# Bravo-Flash_Programmer.net
KiCad netlist of a schematic drawn in EasyEDA
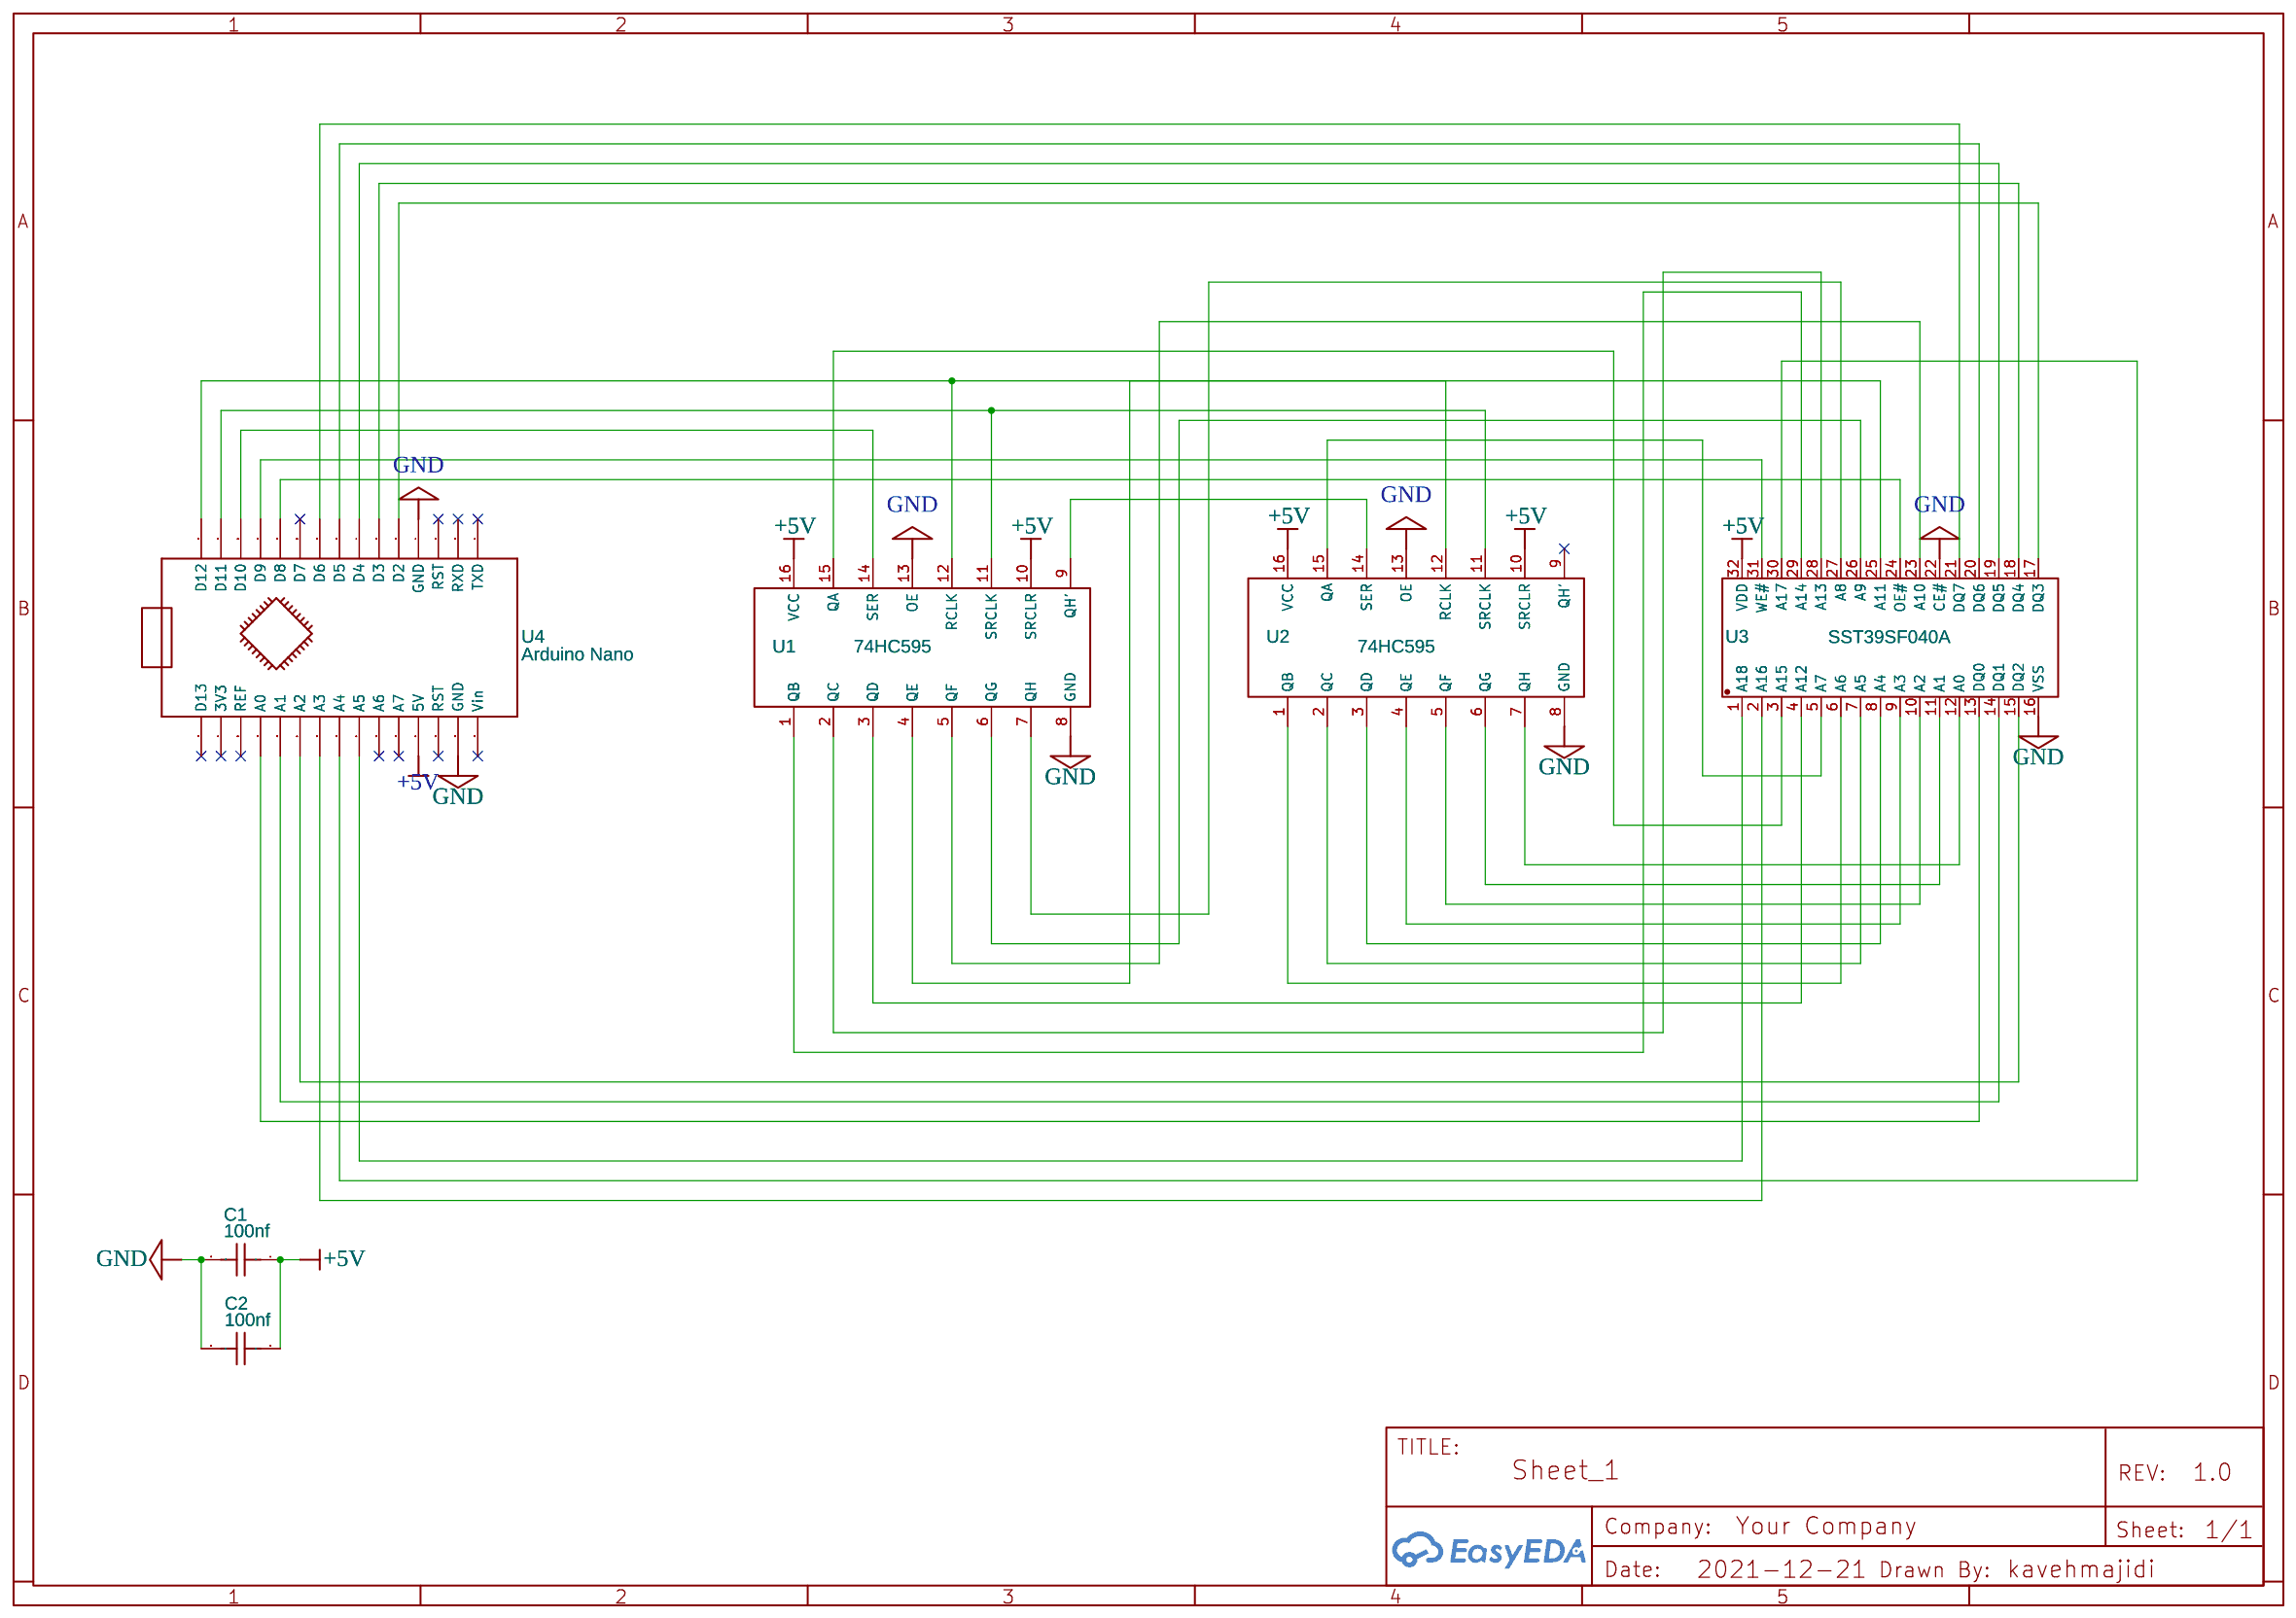
[diagram p0: schematic sheet]

(export (version "E")
  (design (tool "Eeschema 10.0.6"))
  (components
    (comp (ref "C1")
      (value "100nf")
      (fields
        (field (name "BOM_Manufacturer Part") "CC45SL3AD220JYVNA")
        (field (name "BOM_Supplier Part") "C342429")
      )
      (libsource (lib "") (part "CC45SL3AD220JYVNA"))
    )
    (comp (ref "C2")
      (value "100nf")
      (fields
        (field (name "BOM_Manufacturer Part") "CC45SL3AD220JYVNA")
        (field (name "BOM_Supplier Part") "C342429")
      )
      (libsource (lib "") (part "CC45SL3AD220JYVNA"))
    )
    (comp (ref "U1") (value "74HC595") (libsource (lib "") (part "74HC595")))
    (comp (ref "U2") (value "74HC595") (libsource (lib "") (part "74HC595")))
    (comp (ref "U3")
      (value "SST39SF040A")
      (fields
        (field (name "BOM_Manufacturer Part") "SST39SF040-70-4C-PHE")
        (field (name "BOM_Supplier Part") "C220176")
      )
      (libsource (lib "") (part "SST39SF040-70-4C-PHE_C220176"))
    )
    (comp (ref "U4")
      (value "Arduino Nano")
      (fields (field (name "BOM_Manufacturer Part") "ArduinoNano"))
      (libsource (lib "") (part "Arduino Nano"))
    )
  )
  (nets
    (net (code "1") (name "+5V") (class "Default")
      (node (ref "C1") (pin "1") (pinfunction "1_1") (pintype "unspecified"))
      (node (ref "C2") (pin "1") (pinfunction "1_1") (pintype "unspecified"))
      (node (ref "U1") (pin "10") (pinfunction "SRCLR_10") (pintype "unspecified"))
      (node (ref "U1") (pin "16") (pinfunction "VCC_16") (pintype "unspecified"))
      (node (ref "U2") (pin "10") (pinfunction "SRCLR_10") (pintype "unspecified"))
      (node (ref "U2") (pin "16") (pinfunction "VCC_16") (pintype "unspecified"))
      (node (ref "U3") (pin "32") (pinfunction "VDD_32") (pintype "unspecified"))
      (node (ref "U4") (pin "27") (pinfunction "5V_27") (pintype "unspecified"))
    )
    (net (code "2") (name "GND") (class "Default")
      (node (ref "C1") (pin "2") (pinfunction "2_2") (pintype "unspecified"))
      (node (ref "C2") (pin "2") (pinfunction "2_2") (pintype "unspecified"))
      (node (ref "U1") (pin "13") (pinfunction "OE_13") (pintype "unspecified"))
      (node (ref "U1") (pin "8") (pinfunction "GND_8") (pintype "unspecified"))
      (node (ref "U2") (pin "13") (pinfunction "OE_13") (pintype "unspecified"))
      (node (ref "U2") (pin "8") (pinfunction "GND_8") (pintype "unspecified"))
      (node (ref "U3") (pin "16") (pinfunction "VSS_16") (pintype "unspecified"))
      (node (ref "U3") (pin "22") (pinfunction "CE#_22") (pintype "unspecified"))
      (node (ref "U4") (pin "29") (pinfunction "GND_29") (pintype "unspecified"))
      (node (ref "U4") (pin "4") (pinfunction "GND_4") (pintype "unspecified"))
    )
    (net (code "3") (name "Net-(U1-QA)") (class "Default")
      (node (ref "U1") (pin "15") (pinfunction "QA_15") (pintype "unspecified"))
      (node (ref "U3") (pin "3") (pinfunction "A15_3") (pintype "unspecified"))
    )
    (net (code "4") (name "Net-(U1-QB)") (class "Default")
      (node (ref "U1") (pin "1") (pinfunction "QB_1") (pintype "unspecified"))
      (node (ref "U3") (pin "29") (pinfunction "A14_29") (pintype "unspecified"))
    )
    (net (code "5") (name "Net-(U1-QC)") (class "Default")
      (node (ref "U1") (pin "2") (pinfunction "QC_2") (pintype "unspecified"))
      (node (ref "U3") (pin "28") (pinfunction "A13_28") (pintype "unspecified"))
    )
    (net (code "6") (name "Net-(U1-QD)") (class "Default")
      (node (ref "U1") (pin "3") (pinfunction "QD_3") (pintype "unspecified"))
      (node (ref "U3") (pin "4") (pinfunction "A12_4") (pintype "unspecified"))
    )
    (net (code "7") (name "Net-(U1-QE)") (class "Default")
      (node (ref "U1") (pin "4") (pinfunction "QE_4") (pintype "unspecified"))
      (node (ref "U3") (pin "25") (pinfunction "A11_25") (pintype "unspecified"))
    )
    (net (code "8") (name "Net-(U1-QF)") (class "Default")
      (node (ref "U1") (pin "5") (pinfunction "QF_5") (pintype "unspecified"))
      (node (ref "U3") (pin "23") (pinfunction "A10_23") (pintype "unspecified"))
    )
    (net (code "9") (name "Net-(U1-QG)") (class "Default")
      (node (ref "U1") (pin "6") (pinfunction "QG_6") (pintype "unspecified"))
      (node (ref "U3") (pin "26") (pinfunction "A9_26") (pintype "unspecified"))
    )
    (net (code "10") (name "Net-(U1-QH')") (class "Default")
      (node (ref "U1") (pin "9") (pinfunction "QH'_9") (pintype "unspecified"))
      (node (ref "U2") (pin "14") (pinfunction "SER_14") (pintype "unspecified"))
    )
    (net (code "11") (name "Net-(U1-QH)") (class "Default")
      (node (ref "U1") (pin "7") (pinfunction "QH_7") (pintype "unspecified"))
      (node (ref "U3") (pin "27") (pinfunction "A8_27") (pintype "unspecified"))
    )
    (net (code "12") (name "Net-(U1-RCLK)") (class "Default")
      (node (ref "U1") (pin "12") (pinfunction "RCLK_12") (pintype "unspecified"))
      (node (ref "U2") (pin "12") (pinfunction "RCLK_12") (pintype "unspecified"))
      (node (ref "U4") (pin "15") (pinfunction "D12_15") (pintype "unspecified"))
    )
    (net (code "13") (name "Net-(U1-SER)") (class "Default")
      (node (ref "U1") (pin "14") (pinfunction "SER_14") (pintype "unspecified"))
      (node (ref "U4") (pin "13") (pinfunction "D10_13") (pintype "unspecified"))
    )
    (net (code "14") (name "Net-(U1-SRCLK)") (class "Default")
      (node (ref "U1") (pin "11") (pinfunction "SRCLK_11") (pintype "unspecified"))
      (node (ref "U2") (pin "11") (pinfunction "SRCLK_11") (pintype "unspecified"))
      (node (ref "U4") (pin "14") (pinfunction "D11_14") (pintype "unspecified"))
    )
    (net (code "15") (name "Net-(U2-QA)") (class "Default")
      (node (ref "U2") (pin "15") (pinfunction "QA_15") (pintype "unspecified"))
      (node (ref "U3") (pin "5") (pinfunction "A7_5") (pintype "unspecified"))
    )
    (net (code "16") (name "Net-(U2-QB)") (class "Default")
      (node (ref "U2") (pin "1") (pinfunction "QB_1") (pintype "unspecified"))
      (node (ref "U3") (pin "6") (pinfunction "A6_6") (pintype "unspecified"))
    )
    (net (code "17") (name "Net-(U2-QC)") (class "Default")
      (node (ref "U2") (pin "2") (pinfunction "QC_2") (pintype "unspecified"))
      (node (ref "U3") (pin "7") (pinfunction "A5_7") (pintype "unspecified"))
    )
    (net (code "18") (name "Net-(U2-QD)") (class "Default")
      (node (ref "U2") (pin "3") (pinfunction "QD_3") (pintype "unspecified"))
      (node (ref "U3") (pin "8") (pinfunction "A4_8") (pintype "unspecified"))
    )
    (net (code "19") (name "Net-(U2-QE)") (class "Default")
      (node (ref "U2") (pin "4") (pinfunction "QE_4") (pintype "unspecified"))
      (node (ref "U3") (pin "9") (pinfunction "A3_9") (pintype "unspecified"))
    )
    (net (code "20") (name "Net-(U2-QF)") (class "Default")
      (node (ref "U2") (pin "5") (pinfunction "QF_5") (pintype "unspecified"))
      (node (ref "U3") (pin "10") (pinfunction "A2_10") (pintype "unspecified"))
    )
    (net (code "21") (name "Net-(U2-QG)") (class "Default")
      (node (ref "U2") (pin "6") (pinfunction "QG_6") (pintype "unspecified"))
      (node (ref "U3") (pin "11") (pinfunction "A1_11") (pintype "unspecified"))
    )
    (net (code "22") (name "Net-(U2-QH)") (class "Default")
      (node (ref "U2") (pin "7") (pinfunction "QH_7") (pintype "unspecified"))
      (node (ref "U3") (pin "12") (pinfunction "A0_12") (pintype "unspecified"))
    )
    (net (code "23") (name "Net-(U3-A16)") (class "Default")
      (node (ref "U3") (pin "2") (pinfunction "A16_2") (pintype "unspecified"))
      (node (ref "U4") (pin "22") (pinfunction "A3_22") (pintype "unspecified"))
    )
    (net (code "24") (name "Net-(U3-A17)") (class "Default")
      (node (ref "U3") (pin "30") (pinfunction "A17_30") (pintype "unspecified"))
      (node (ref "U4") (pin "23") (pinfunction "A4_23") (pintype "unspecified"))
    )
    (net (code "25") (name "Net-(U3-A18)") (class "Default")
      (node (ref "U3") (pin "1") (pinfunction "A18_1") (pintype "unspecified"))
      (node (ref "U4") (pin "24") (pinfunction "A5_24") (pintype "unspecified"))
    )
    (net (code "26") (name "Net-(U3-DQ0)") (class "Default")
      (node (ref "U3") (pin "13") (pinfunction "DQ0_13") (pintype "unspecified"))
      (node (ref "U4") (pin "19") (pinfunction "A0_19") (pintype "unspecified"))
    )
    (net (code "27") (name "Net-(U3-DQ1)") (class "Default")
      (node (ref "U3") (pin "14") (pinfunction "DQ1_14") (pintype "unspecified"))
      (node (ref "U4") (pin "20") (pinfunction "A1_20") (pintype "unspecified"))
    )
    (net (code "28") (name "Net-(U3-DQ2)") (class "Default")
      (node (ref "U3") (pin "15") (pinfunction "DQ2_15") (pintype "unspecified"))
      (node (ref "U4") (pin "21") (pinfunction "A2_21") (pintype "unspecified"))
    )
    (net (code "29") (name "Net-(U3-DQ3)") (class "Default")
      (node (ref "U3") (pin "17") (pinfunction "DQ3_17") (pintype "unspecified"))
      (node (ref "U4") (pin "5") (pinfunction "D2_5") (pintype "unspecified"))
    )
    (net (code "30") (name "Net-(U3-DQ4)") (class "Default")
      (node (ref "U3") (pin "18") (pinfunction "DQ4_18") (pintype "unspecified"))
      (node (ref "U4") (pin "6") (pinfunction "D3_6") (pintype "unspecified"))
    )
    (net (code "31") (name "Net-(U3-DQ5)") (class "Default")
      (node (ref "U3") (pin "19") (pinfunction "DQ5_19") (pintype "unspecified"))
      (node (ref "U4") (pin "7") (pinfunction "D4_7") (pintype "unspecified"))
    )
    (net (code "32") (name "Net-(U3-DQ6)") (class "Default")
      (node (ref "U3") (pin "20") (pinfunction "DQ6_20") (pintype "unspecified"))
      (node (ref "U4") (pin "8") (pinfunction "D5_8") (pintype "unspecified"))
    )
    (net (code "33") (name "Net-(U3-DQ7)") (class "Default")
      (node (ref "U3") (pin "21") (pinfunction "DQ7_21") (pintype "unspecified"))
      (node (ref "U4") (pin "9") (pinfunction "D6_9") (pintype "unspecified"))
    )
    (net (code "34") (name "Net-(U3-OE#)") (class "Default")
      (node (ref "U3") (pin "24") (pinfunction "OE#_24") (pintype "unspecified"))
      (node (ref "U4") (pin "11") (pinfunction "D8_11") (pintype "unspecified"))
    )
    (net (code "35") (name "Net-(U3-WE#)") (class "Default")
      (node (ref "U3") (pin "31") (pinfunction "WE#_31") (pintype "unspecified"))
      (node (ref "U4") (pin "12") (pinfunction "D9_12") (pintype "unspecified"))
    )
    (net (code "36") (name "unconnected-(U2-QH'-Pad9)") (class "Default")
      (node (ref "U2") (pin "9") (pinfunction "QH'_9") (pintype "unspecified+no_connect"))
    )
    (net (code "37") (name "unconnected-(U4-3V3-Pad17)") (class "Default")
      (node (ref "U4") (pin "17") (pinfunction "3V3_17") (pintype "unspecified+no_connect"))
    )
    (net (code "38") (name "unconnected-(U4-A6-Pad25)") (class "Default")
      (node (ref "U4") (pin "25") (pinfunction "A6_25") (pintype "unspecified+no_connect"))
    )
    (net (code "39") (name "unconnected-(U4-A7-Pad26)") (class "Default")
      (node (ref "U4") (pin "26") (pinfunction "A7_26") (pintype "unspecified+no_connect"))
    )
    (net (code "40") (name "unconnected-(U4-D7-Pad10)") (class "Default")
      (node (ref "U4") (pin "10") (pinfunction "D7_10") (pintype "unspecified+no_connect"))
    )
    (net (code "41") (name "unconnected-(U4-D13-Pad16)") (class "Default")
      (node (ref "U4") (pin "16") (pinfunction "D13_16") (pintype "unspecified+no_connect"))
    )
    (net (code "42") (name "unconnected-(U4-REF-Pad18)") (class "Default")
      (node (ref "U4") (pin "18") (pinfunction "REF_18") (pintype "unspecified+no_connect"))
    )
    (net (code "43") (name "unconnected-(U4-RST-Pad3)") (class "Default")
      (node (ref "U4") (pin "3") (pinfunction "RST_3") (pintype "unspecified+no_connect"))
    )
    (net (code "44") (name "unconnected-(U4-RST-Pad28)") (class "Default")
      (node (ref "U4") (pin "28") (pinfunction "RST_28") (pintype "unspecified+no_connect"))
    )
    (net (code "45") (name "unconnected-(U4-RXD-Pad2)") (class "Default")
      (node (ref "U4") (pin "2") (pinfunction "RXD_2") (pintype "unspecified+no_connect"))
    )
    (net (code "46") (name "unconnected-(U4-TXD-Pad1)") (class "Default")
      (node (ref "U4") (pin "1") (pinfunction "TXD_1") (pintype "unspecified+no_connect"))
    )
    (net (code "47") (name "unconnected-(U4-Vin-Pad30)") (class "Default")
      (node (ref "U4") (pin "30") (pinfunction "Vin_30") (pintype "unspecified+no_connect"))
    )
  )
)
